# winder.net
KiCad netlist of a schematic drawn in EAGLE
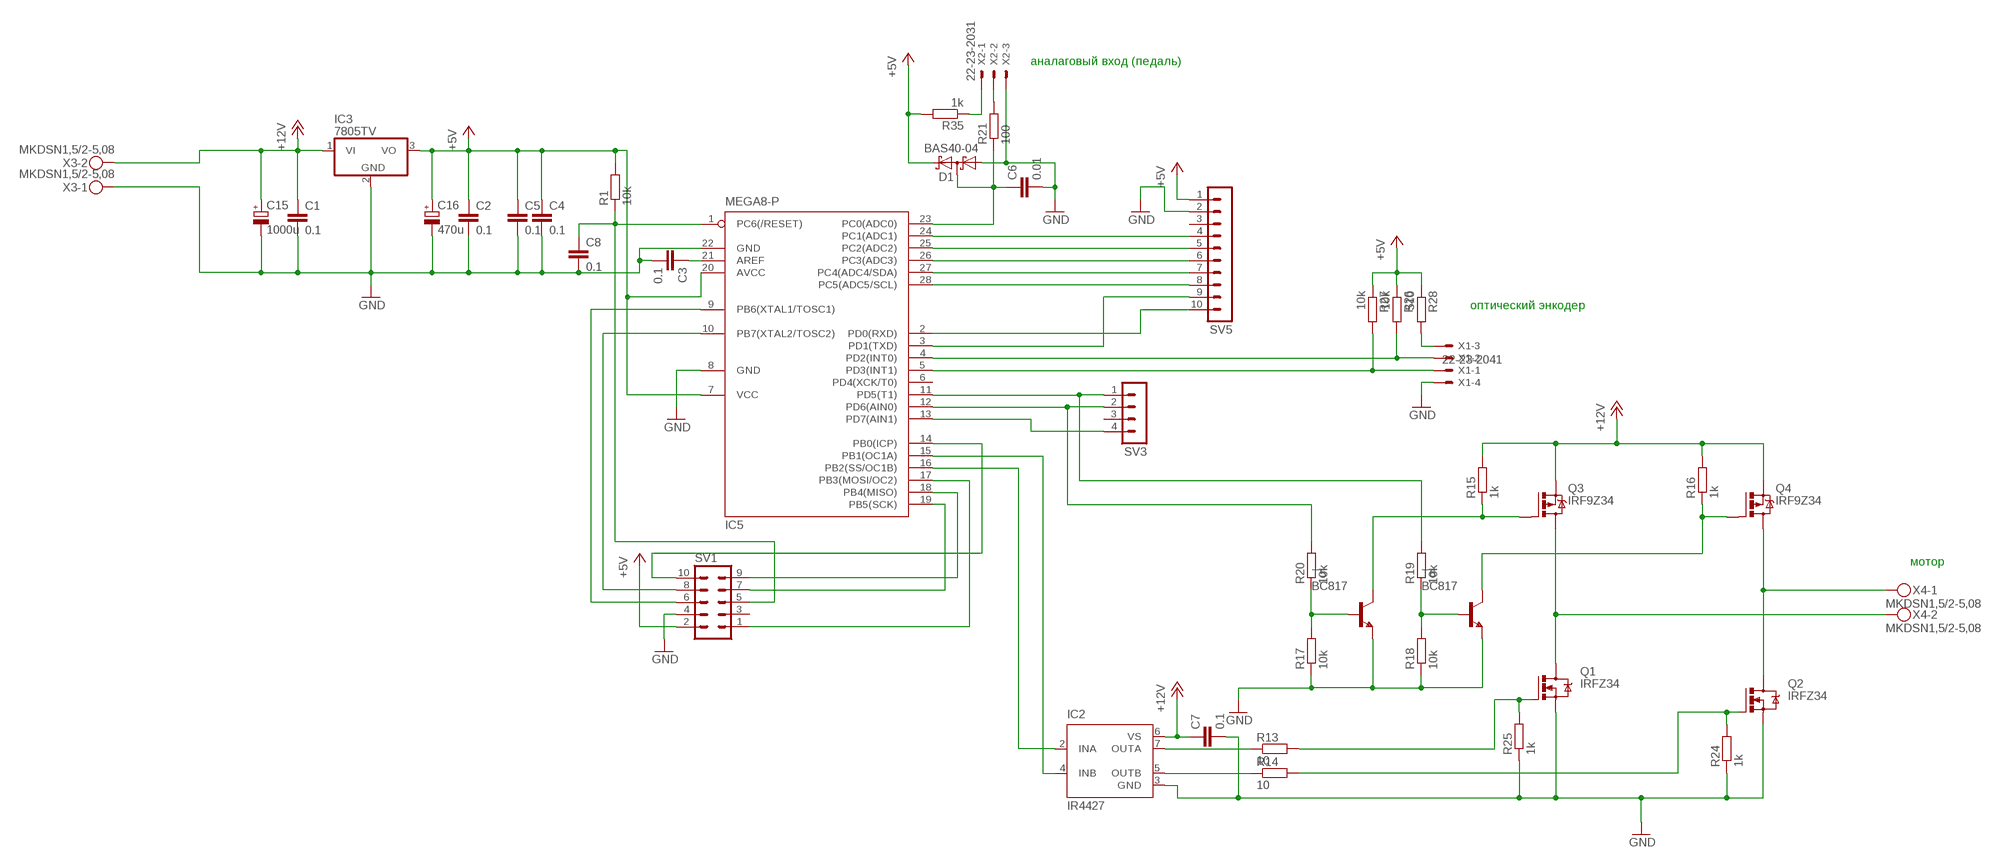
[diagram p0: schematic, sheet 1]

(export (version "E")
  (design (tool "Eeschema 10.0.6"))
  (components
    (comp (ref "C1")
      (value "0.1")
      (footprint "eagle-import:C0805")
      (libsource (lib "eagle-import") (part "C-EUC0805"))
    )
    (comp (ref "C2")
      (value "0.1")
      (footprint "eagle-import:C0805")
      (libsource (lib "eagle-import") (part "C-EUC0805"))
    )
    (comp (ref "C3")
      (value "0.1")
      (footprint "eagle-import:C0805")
      (libsource (lib "eagle-import") (part "C-EUC0805"))
    )
    (comp (ref "C4")
      (value "0.1")
      (footprint "eagle-import:C0805")
      (libsource (lib "eagle-import") (part "C-EUC0805"))
    )
    (comp (ref "C5")
      (value "0.1")
      (footprint "eagle-import:C0805")
      (libsource (lib "eagle-import") (part "C-EUC0805"))
    )
    (comp (ref "C6")
      (value "0.01")
      (footprint "eagle-import:C0805")
      (libsource (lib "eagle-import") (part "C-EUC0805"))
    )
    (comp (ref "C7")
      (value "0.1")
      (footprint "eagle-import:C0805")
      (libsource (lib "eagle-import") (part "C-EUC0805"))
    )
    (comp (ref "C8")
      (value "0.1")
      (footprint "eagle-import:C0805")
      (libsource (lib "eagle-import") (part "C-EUC0805"))
    )
    (comp (ref "C15")
      (value "1000u")
      (footprint "eagle-import:E3,5-10")
      (libsource (lib "eagle-import") (part "CPOL-EUE3.5-10"))
    )
    (comp (ref "C16")
      (value "470u")
      (footprint "eagle-import:E3,5-10")
      (libsource (lib "eagle-import") (part "CPOL-EUE3.5-10"))
    )
    (comp (ref "D1")
      (value "BAS40-04")
      (footprint "eagle-import:SOT23")
      (libsource (lib "eagle-import") (part "BAS40-04"))
    )
    (comp (ref "IC2")
      (value "IR4427")
      (footprint "eagle-import:DIL08")
      (fields (field (name "MF") "INTERNATIONAL RECTIFIER(IR)"))
      (libsource (lib "eagle-import") (part "IR4427"))
    )
    (comp (ref "IC3")
      (value "7805TV")
      (footprint "eagle-import:TO220V")
      (libsource (lib "eagle-import") (part "78TV05"))
    )
    (comp (ref "IC5")
      (value "MEGA8-P")
      (footprint "eagle-import:DIL28-3")
      (libsource (lib "eagle-import") (part "MEGA8-P"))
    )
    (comp (ref "Q1")
      (value "IRFZ34")
      (footprint "eagle-import:TO220BV")
      (libsource (lib "eagle-import") (part "IRF530"))
    )
    (comp (ref "Q2")
      (value "IRFZ34")
      (footprint "eagle-import:TO220BV")
      (libsource (lib "eagle-import") (part "IRF530"))
    )
    (comp (ref "Q3")
      (value "IRF9Z34")
      (footprint "eagle-import:TO220BV")
      (libsource (lib "eagle-import") (part "IRF9530"))
    )
    (comp (ref "Q4")
      (value "IRF9Z34")
      (footprint "eagle-import:TO220BV")
      (libsource (lib "eagle-import") (part "IRF9530"))
    )
    (comp (ref "R1")
      (value "10k")
      (footprint "eagle-import:R0805")
      (libsource (lib "eagle-import") (part "R-EU_R0805"))
    )
    (comp (ref "R13")
      (value "10")
      (footprint "eagle-import:R0805")
      (libsource (lib "eagle-import") (part "R-EU_R0805"))
    )
    (comp (ref "R14")
      (value "10")
      (footprint "eagle-import:R0805")
      (libsource (lib "eagle-import") (part "R-EU_R0805"))
    )
    (comp (ref "R15")
      (value "1k")
      (footprint "eagle-import:R0805")
      (libsource (lib "eagle-import") (part "R-EU_R0805"))
    )
    (comp (ref "R16")
      (value "1k")
      (footprint "eagle-import:R0805")
      (libsource (lib "eagle-import") (part "R-EU_R0805"))
    )
    (comp (ref "R17")
      (value "10k")
      (footprint "eagle-import:R0805")
      (libsource (lib "eagle-import") (part "R-EU_R0805"))
    )
    (comp (ref "R18")
      (value "10k")
      (footprint "eagle-import:R0805")
      (libsource (lib "eagle-import") (part "R-EU_R0805"))
    )
    (comp (ref "R19")
      (value "10k")
      (footprint "eagle-import:R0805")
      (libsource (lib "eagle-import") (part "R-EU_R0805"))
    )
    (comp (ref "R20")
      (value "10k")
      (footprint "eagle-import:R0805")
      (libsource (lib "eagle-import") (part "R-EU_R0805"))
    )
    (comp (ref "R21")
      (value "100")
      (footprint "eagle-import:R0805")
      (libsource (lib "eagle-import") (part "R-EU_R0805"))
    )
    (comp (ref "R24")
      (value "1k")
      (footprint "eagle-import:R0805")
      (libsource (lib "eagle-import") (part "R-EU_R0805"))
    )
    (comp (ref "R25")
      (value "1k")
      (footprint "eagle-import:R0805")
      (libsource (lib "eagle-import") (part "R-EU_R0805"))
    )
    (comp (ref "R26")
      (value "10k")
      (footprint "eagle-import:R0805")
      (libsource (lib "eagle-import") (part "R-EU_R0805"))
    )
    (comp (ref "R27")
      (value "10k")
      (footprint "eagle-import:R0805")
      (libsource (lib "eagle-import") (part "R-EU_R0805"))
    )
    (comp (ref "R28")
      (value "510")
      (footprint "eagle-import:R0805")
      (libsource (lib "eagle-import") (part "R-EU_R0805"))
    )
    (comp (ref "R35")
      (value "1k")
      (footprint "eagle-import:R0805")
      (libsource (lib "eagle-import") (part "R-EU_R0805"))
    )
    (comp (ref "SV1")
      (value "ML10")
      (footprint "eagle-import:ML10")
      (libsource (lib "eagle-import") (part "ML10"))
    )
    (comp (ref "SV3")
      (value "MA04-1")
      (footprint "eagle-import:MA04-1")
      (libsource (lib "eagle-import") (part "MA04-1"))
    )
    (comp (ref "SV5")
      (value "MA10-1")
      (footprint "eagle-import:MA10-1")
      (libsource (lib "eagle-import") (part "MA10-1"))
    )
    (comp (ref "T5")
      (value "BC817")
      (footprint "eagle-import:SOT23-BEC")
      (libsource (lib "eagle-import") (part "-NPN-SOT23-BECBC817-16"))
    )
    (comp (ref "T6")
      (value "BC817")
      (footprint "eagle-import:SOT23-BEC")
      (libsource (lib "eagle-import") (part "-NPN-SOT23-BECBC817-16"))
    )
    (comp (ref "X1")
      (value "22-23-2041")
      (footprint "eagle-import:22-23-2041")
      (fields (field (name "MF") "MOLEX"))
      (libsource (lib "eagle-import") (part "22-23-2041"))
    )
    (comp (ref "X2")
      (value "22-23-2031")
      (footprint "eagle-import:22-23-2031")
      (fields (field (name "MF") "MOLEX"))
      (libsource (lib "eagle-import") (part "22-23-2031"))
    )
    (comp (ref "X3")
      (value "MKDSN1,5/2-5,08")
      (footprint "eagle-import:MKDSN1,5_2-5,08")
      (libsource (lib "eagle-import") (part "MKDSN1,5/2-5,08"))
    )
    (comp (ref "X4")
      (value "MKDSN1,5/2-5,08")
      (footprint "eagle-import:MKDSN1,5_2-5,08")
      (libsource (lib "eagle-import") (part "MKDSN1,5/2-5,08"))
    )
  )
  (nets
    (net (code "1") (name "+5V") (class "Default")
      (node (ref "C16") (pin "+") (pinfunction "+_+") (pintype "passive"))
      (node (ref "C2") (pin "1") (pinfunction "1_1") (pintype "passive"))
      (node (ref "C4") (pin "1") (pinfunction "1_1") (pintype "passive"))
      (node (ref "C5") (pin "1") (pinfunction "1_1") (pintype "passive"))
      (node (ref "D1") (pin "2") (pinfunction "C2_2") (pintype "passive"))
      (node (ref "IC3") (pin "3") (pinfunction "VO_3") (pintype "passive"))
      (node (ref "IC5") (pin "20") (pinfunction "AVCC_20") (pintype "power_in"))
      (node (ref "IC5") (pin "7") (pinfunction "VCC_7") (pintype "power_in"))
      (node (ref "R1") (pin "2") (pinfunction "2_2") (pintype "passive"))
      (node (ref "R26") (pin "1") (pinfunction "1_1") (pintype "passive"))
      (node (ref "R27") (pin "1") (pinfunction "1_1") (pintype "passive"))
      (node (ref "R28") (pin "1") (pinfunction "1_1") (pintype "passive"))
      (node (ref "R35") (pin "2") (pinfunction "2_2") (pintype "passive"))
      (node (ref "SV1") (pin "2") (pinfunction "2_2") (pintype "passive"))
      (node (ref "SV5") (pin "1") (pinfunction "1_1") (pintype "passive"))
    )
    (net (code "2") (name "+12V") (class "Default")
      (node (ref "C1") (pin "1") (pinfunction "1_1") (pintype "passive"))
      (node (ref "C15") (pin "+") (pinfunction "+_+") (pintype "passive"))
      (node (ref "C7") (pin "1") (pinfunction "1_1") (pintype "passive"))
      (node (ref "IC2") (pin "6") (pinfunction "VS_6") (pintype "power_in"))
      (node (ref "IC3") (pin "1") (pinfunction "VI_1") (pintype "input"))
      (node (ref "Q3") (pin "S") (pinfunction "S_S") (pintype "passive"))
      (node (ref "Q4") (pin "S") (pinfunction "S_S") (pintype "passive"))
      (node (ref "R15") (pin "2") (pinfunction "2_2") (pintype "passive"))
      (node (ref "R16") (pin "2") (pinfunction "2_2") (pintype "passive"))
      (node (ref "X3") (pin "2") (pinfunction "KL_2") (pintype "passive"))
    )
    (net (code "3") (name "GND") (class "Default")
      (node (ref "C1") (pin "2") (pinfunction "2_2") (pintype "passive"))
      (node (ref "C15") (pin "-") (pinfunction "-_-") (pintype "passive"))
      (node (ref "C16") (pin "-") (pinfunction "-_-") (pintype "passive"))
      (node (ref "C2") (pin "2") (pinfunction "2_2") (pintype "passive"))
      (node (ref "C3") (pin "2") (pinfunction "2_2") (pintype "passive"))
      (node (ref "C4") (pin "2") (pinfunction "2_2") (pintype "passive"))
      (node (ref "C5") (pin "2") (pinfunction "2_2") (pintype "passive"))
      (node (ref "C6") (pin "2") (pinfunction "2_2") (pintype "passive"))
      (node (ref "C7") (pin "2") (pinfunction "2_2") (pintype "passive"))
      (node (ref "C8") (pin "2") (pinfunction "2_2") (pintype "passive"))
      (node (ref "D1") (pin "1") (pinfunction "A1_1") (pintype "passive"))
      (node (ref "IC2") (pin "3") (pinfunction "GND_3") (pintype "power_in"))
      (node (ref "IC3") (pin "2") (pinfunction "GND_2") (pintype "passive"))
      (node (ref "IC5") (pin "22") (pinfunction "GND_22") (pintype "power_in"))
      (node (ref "IC5") (pin "8") (pinfunction "GND_8") (pintype "power_in"))
      (node (ref "Q1") (pin "S") (pinfunction "S_S") (pintype "passive"))
      (node (ref "Q2") (pin "S") (pinfunction "S_S") (pintype "passive"))
      (node (ref "R17") (pin "1") (pinfunction "1_1") (pintype "passive"))
      (node (ref "R18") (pin "1") (pinfunction "1_1") (pintype "passive"))
      (node (ref "R24") (pin "1") (pinfunction "1_1") (pintype "passive"))
      (node (ref "R25") (pin "1") (pinfunction "1_1") (pintype "passive"))
      (node (ref "SV1") (pin "4") (pinfunction "4_4") (pintype "passive"))
      (node (ref "SV5") (pin "2") (pinfunction "2_2") (pintype "passive"))
      (node (ref "T5") (pin "E") (pinfunction "E_E") (pintype "passive"))
      (node (ref "T6") (pin "E") (pinfunction "E_E") (pintype "passive"))
      (node (ref "X1") (pin "4") (pinfunction "S_4") (pintype "passive"))
      (node (ref "X2") (pin "3") (pinfunction "S_3") (pintype "passive"))
      (node (ref "X3") (pin "1") (pinfunction "KL_1") (pintype "passive"))
    )
    (net (code "4") (name "Net-(D1-C1A2)") (class "Default")
      (node (ref "C6") (pin "1") (pinfunction "1_1") (pintype "passive"))
      (node (ref "D1") (pin "3") (pinfunction "C1A2_3") (pintype "passive"))
      (node (ref "IC5") (pin "23") (pinfunction "PC0(ADC0)_23") (pintype "bidirectional"))
      (node (ref "R21") (pin "1") (pinfunction "1_1") (pintype "passive"))
    )
    (net (code "5") (name "Net-(IC2-INA)") (class "Default")
      (node (ref "IC2") (pin "2") (pinfunction "INA_2") (pintype "input"))
      (node (ref "IC5") (pin "16") (pinfunction "PB2(SS/OC1B)_16") (pintype "bidirectional"))
    )
    (net (code "6") (name "Net-(IC2-INB)") (class "Default")
      (node (ref "IC2") (pin "4") (pinfunction "INB_4") (pintype "input"))
      (node (ref "IC5") (pin "15") (pinfunction "PB1(OC1A)_15") (pintype "bidirectional"))
    )
    (net (code "7") (name "Net-(IC2-OUTA)") (class "Default")
      (node (ref "IC2") (pin "7") (pinfunction "OUTA_7") (pintype "output"))
      (node (ref "R13") (pin "1") (pinfunction "1_1") (pintype "passive"))
    )
    (net (code "8") (name "Net-(IC2-OUTB)") (class "Default")
      (node (ref "IC2") (pin "5") (pinfunction "OUTB_5") (pintype "output"))
      (node (ref "R14") (pin "1") (pinfunction "1_1") (pintype "passive"))
    )
    (net (code "9") (name "Net-(IC5-AREF)") (class "Default")
      (node (ref "C3") (pin "1") (pinfunction "1_1") (pintype "passive"))
      (node (ref "IC5") (pin "21") (pinfunction "AREF_21") (pintype "passive"))
    )
    (net (code "10") (name "Net-(IC5-PB0(ICP))") (class "Default")
      (node (ref "IC5") (pin "14") (pinfunction "PB0(ICP)_14") (pintype "bidirectional"))
      (node (ref "SV1") (pin "10") (pinfunction "10_10") (pintype "passive"))
    )
    (net (code "11") (name "Net-(IC5-PB3(MOSI{slash}OC2))") (class "Default")
      (node (ref "IC5") (pin "17") (pinfunction "PB3(MOSI/OC2)_17") (pintype "bidirectional"))
      (node (ref "SV1") (pin "1") (pinfunction "1_1") (pintype "passive"))
    )
    (net (code "12") (name "Net-(IC5-PB4(MISO))") (class "Default")
      (node (ref "IC5") (pin "18") (pinfunction "PB4(MISO)_18") (pintype "bidirectional"))
      (node (ref "SV1") (pin "9") (pinfunction "9_9") (pintype "passive"))
    )
    (net (code "13") (name "Net-(IC5-PB5(SCK))") (class "Default")
      (node (ref "IC5") (pin "19") (pinfunction "PB5(SCK)_19") (pintype "bidirectional"))
      (node (ref "SV1") (pin "7") (pinfunction "7_7") (pintype "passive"))
    )
    (net (code "14") (name "Net-(IC5-PB6(XTAL1{slash}TOSC1))") (class "Default")
      (node (ref "IC5") (pin "9") (pinfunction "PB6(XTAL1/TOSC1)_9") (pintype "bidirectional"))
      (node (ref "SV1") (pin "6") (pinfunction "6_6") (pintype "passive"))
    )
    (net (code "15") (name "Net-(IC5-PB7(XTAL2{slash}TOSC2))") (class "Default")
      (node (ref "IC5") (pin "10") (pinfunction "PB7(XTAL2/TOSC2)_10") (pintype "bidirectional"))
      (node (ref "SV1") (pin "8") (pinfunction "8_8") (pintype "passive"))
    )
    (net (code "16") (name "Net-(IC5-PC1(ADC1))") (class "Default")
      (node (ref "IC5") (pin "24") (pinfunction "PC1(ADC1)_24") (pintype "bidirectional"))
      (node (ref "SV5") (pin "4") (pinfunction "4_4") (pintype "passive"))
    )
    (net (code "17") (name "Net-(IC5-PC2(ADC2))") (class "Default")
      (node (ref "IC5") (pin "25") (pinfunction "PC2(ADC2)_25") (pintype "bidirectional"))
      (node (ref "SV5") (pin "5") (pinfunction "5_5") (pintype "passive"))
    )
    (net (code "18") (name "Net-(IC5-PC3(ADC3))") (class "Default")
      (node (ref "IC5") (pin "26") (pinfunction "PC3(ADC3)_26") (pintype "bidirectional"))
      (node (ref "SV5") (pin "6") (pinfunction "6_6") (pintype "passive"))
    )
    (net (code "19") (name "Net-(IC5-PC4(ADC4{slash}SDA))") (class "Default")
      (node (ref "IC5") (pin "27") (pinfunction "PC4(ADC4/SDA)_27") (pintype "bidirectional"))
      (node (ref "SV5") (pin "7") (pinfunction "7_7") (pintype "passive"))
    )
    (net (code "20") (name "Net-(IC5-PC5(ADC5{slash}SCL))") (class "Default")
      (node (ref "IC5") (pin "28") (pinfunction "PC5(ADC5/SCL)_28") (pintype "bidirectional"))
      (node (ref "SV5") (pin "8") (pinfunction "8_8") (pintype "passive"))
    )
    (net (code "21") (name "Net-(IC5-PC6({slash}RESET))") (class "Default")
      (node (ref "C8") (pin "1") (pinfunction "1_1") (pintype "passive"))
      (node (ref "IC5") (pin "1") (pinfunction "PC6(/RESET)_1") (pintype "bidirectional"))
      (node (ref "R1") (pin "1") (pinfunction "1_1") (pintype "passive"))
      (node (ref "SV1") (pin "5") (pinfunction "5_5") (pintype "passive"))
    )
    (net (code "22") (name "Net-(IC5-PD0(RXD))") (class "Default")
      (node (ref "IC5") (pin "2") (pinfunction "PD0(RXD)_2") (pintype "bidirectional"))
      (node (ref "SV5") (pin "10") (pinfunction "10_10") (pintype "passive"))
    )
    (net (code "23") (name "Net-(IC5-PD1(TXD))") (class "Default")
      (node (ref "IC5") (pin "3") (pinfunction "PD1(TXD)_3") (pintype "bidirectional"))
      (node (ref "SV5") (pin "9") (pinfunction "9_9") (pintype "passive"))
    )
    (net (code "24") (name "Net-(IC5-PD2(INT0))") (class "Default")
      (node (ref "IC5") (pin "4") (pinfunction "PD2(INT0)_4") (pintype "bidirectional"))
      (node (ref "R26") (pin "2") (pinfunction "2_2") (pintype "passive"))
      (node (ref "X1") (pin "2") (pinfunction "S_2") (pintype "passive"))
    )
    (net (code "25") (name "Net-(IC5-PD3(INT1))") (class "Default")
      (node (ref "IC5") (pin "5") (pinfunction "PD3(INT1)_5") (pintype "bidirectional"))
      (node (ref "R27") (pin "2") (pinfunction "2_2") (pintype "passive"))
      (node (ref "X1") (pin "1") (pinfunction "S_1") (pintype "passive"))
    )
    (net (code "26") (name "Net-(IC5-PD5(T1))") (class "Default")
      (node (ref "IC5") (pin "11") (pinfunction "PD5(T1)_11") (pintype "bidirectional"))
      (node (ref "R19") (pin "2") (pinfunction "2_2") (pintype "passive"))
      (node (ref "SV3") (pin "1") (pinfunction "1_1") (pintype "passive"))
    )
    (net (code "27") (name "Net-(IC5-PD6(AIN0))") (class "Default")
      (node (ref "IC5") (pin "12") (pinfunction "PD6(AIN0)_12") (pintype "bidirectional"))
      (node (ref "R20") (pin "2") (pinfunction "2_2") (pintype "passive"))
      (node (ref "SV3") (pin "2") (pinfunction "2_2") (pintype "passive"))
    )
    (net (code "28") (name "Net-(IC5-PD7(AIN1))") (class "Default")
      (node (ref "IC5") (pin "13") (pinfunction "PD7(AIN1)_13") (pintype "bidirectional"))
      (node (ref "SV3") (pin "4") (pinfunction "4_4") (pintype "passive"))
    )
    (net (code "29") (name "Net-(Q1-PadG)") (class "Default")
      (node (ref "Q1") (pin "G") (pinfunction "G_G") (pintype "passive"))
      (node (ref "R13") (pin "2") (pinfunction "2_2") (pintype "passive"))
      (node (ref "R25") (pin "2") (pinfunction "2_2") (pintype "passive"))
    )
    (net (code "30") (name "Net-(Q2-PadG)") (class "Default")
      (node (ref "Q2") (pin "G") (pinfunction "G_G") (pintype "passive"))
      (node (ref "R14") (pin "2") (pinfunction "2_2") (pintype "passive"))
      (node (ref "R24") (pin "2") (pinfunction "2_2") (pintype "passive"))
    )
    (net (code "31") (name "Net-(Q3-PadG)") (class "Default")
      (node (ref "Q3") (pin "G") (pinfunction "G_G") (pintype "passive"))
      (node (ref "R15") (pin "1") (pinfunction "1_1") (pintype "passive"))
      (node (ref "T5") (pin "C") (pinfunction "C_C") (pintype "passive"))
    )
    (net (code "32") (name "Net-(Q4-PadG)") (class "Default")
      (node (ref "Q4") (pin "G") (pinfunction "G_G") (pintype "passive"))
      (node (ref "R16") (pin "1") (pinfunction "1_1") (pintype "passive"))
      (node (ref "T6") (pin "C") (pinfunction "C_C") (pintype "passive"))
    )
    (net (code "33") (name "Net-(R17-Pad2)") (class "Default")
      (node (ref "R17") (pin "2") (pinfunction "2_2") (pintype "passive"))
      (node (ref "R20") (pin "1") (pinfunction "1_1") (pintype "passive"))
      (node (ref "T5") (pin "B") (pinfunction "B_B") (pintype "passive"))
    )
    (net (code "34") (name "Net-(R18-Pad2)") (class "Default")
      (node (ref "R18") (pin "2") (pinfunction "2_2") (pintype "passive"))
      (node (ref "R19") (pin "1") (pinfunction "1_1") (pintype "passive"))
      (node (ref "T6") (pin "B") (pinfunction "B_B") (pintype "passive"))
    )
    (net (code "35") (name "Net-(X1C-S)") (class "Default")
      (node (ref "R28") (pin "2") (pinfunction "2_2") (pintype "passive"))
      (node (ref "X1") (pin "3") (pinfunction "S_3") (pintype "passive"))
    )
    (net (code "36") (name "Net-(X2A-S)") (class "Default")
      (node (ref "R35") (pin "1") (pinfunction "1_1") (pintype "passive"))
      (node (ref "X2") (pin "1") (pinfunction "S_1") (pintype "passive"))
    )
    (net (code "37") (name "Net-(X2B-S)") (class "Default")
      (node (ref "R21") (pin "2") (pinfunction "2_2") (pintype "passive"))
      (node (ref "X2") (pin "2") (pinfunction "S_2") (pintype "passive"))
    )
    (net (code "38") (name "Net-(X4A-KL)") (class "Default")
      (node (ref "Q2") (pin "D") (pinfunction "D_D") (pintype "passive"))
      (node (ref "Q4") (pin "D") (pinfunction "D_D") (pintype "passive"))
      (node (ref "X4") (pin "1") (pinfunction "KL_1") (pintype "passive"))
    )
    (net (code "39") (name "Net-(X4B-KL)") (class "Default")
      (node (ref "Q1") (pin "D") (pinfunction "D_D") (pintype "passive"))
      (node (ref "Q3") (pin "D") (pinfunction "D_D") (pintype "passive"))
      (node (ref "X4") (pin "2") (pinfunction "KL_2") (pintype "passive"))
    )
    (net (code "40") (name "unconnected-(IC5-PD4(XCK{slash}T0)-Pad6)") (class "Default")
      (node (ref "IC5") (pin "6") (pinfunction "PD4(XCK/T0)_6") (pintype "bidirectional"))
    )
    (net (code "41") (name "unconnected-(SV1-Pad3)") (class "Default")
      (node (ref "SV1") (pin "3") (pinfunction "3_3") (pintype "passive"))
    )
    (net (code "42") (name "unconnected-(SV3-Pad3)") (class "Default")
      (node (ref "SV3") (pin "3") (pinfunction "3_3") (pintype "passive"))
    )
    (net (code "43") (name "unconnected-(SV5-Pad3)") (class "Default")
      (node (ref "SV5") (pin "3") (pinfunction "3_3") (pintype "passive"))
    )
  )
)
